# 3w-rgb-led-connector-mk-5_1.net
KiCad netlist of a schematic drawn in EAGLE
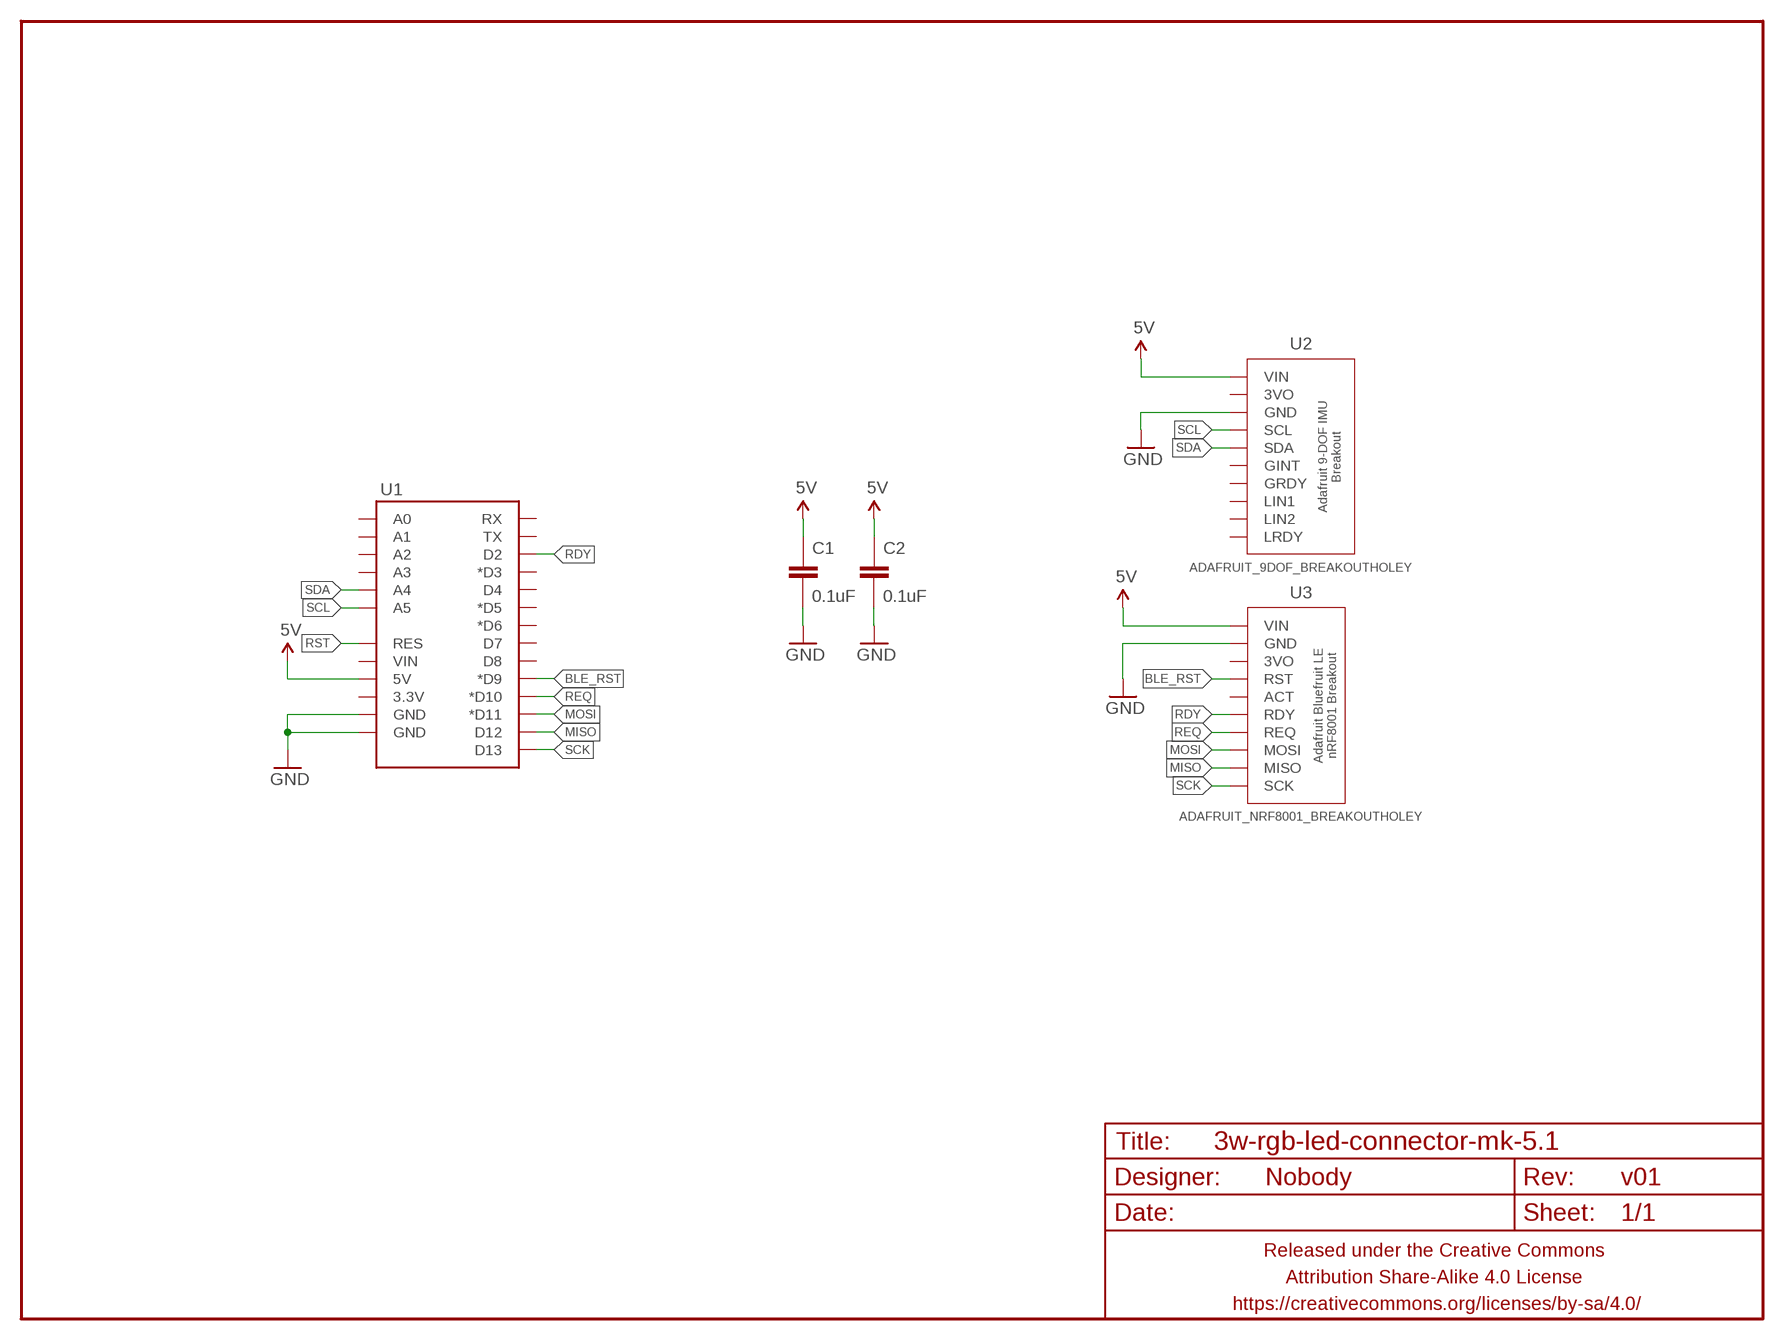
[diagram p0: schematic, sheet 1]

(export (version "E")
  (design (tool "Eeschema 10.0.6"))
  (components
    (comp (ref "C1")
      (value "0.1uF")
      (footprint "eagle-import:C025-024X044")
      (libsource (lib "eagle-import") (part "CAPACITOR-CERAMIC025-024X044"))
    )
    (comp (ref "C2")
      (value "0.1uF")
      (footprint "eagle-import:C025-024X044")
      (libsource (lib "eagle-import") (part "CAPACITOR-CERAMIC025-024X044"))
    )
    (comp (ref "FRAME1")
      (value "FRAME-LETTERNO_PACKAGE")
      (footprint "eagle-import:DUMMY")
      (fields (field (name "DESIGNER") "Nobody"))
      (libsource (lib "eagle-import") (part "FRAME-LETTERNO_PACKAGE"))
    )
    (comp (ref "U1")
      (value "ARDUINO_SHIELD_SMALLER")
      (footprint "eagle-import:ARDUINO_SHIELD_NOOUTLINE_INSIDE_SMALLER")
      (libsource (lib "eagle-import") (part "ARDUINO_SHIELD_SMALLER"))
    )
    (comp (ref "U2")
      (value "ADAFRUIT_9DOF_BREAKOUTHOLEY")
      (footprint "eagle-import:ADAFRUIT_9DOF_BREAKOUT_HOLEY")
      (libsource (lib "eagle-import") (part "ADAFRUIT_9DOF_BREAKOUTHOLEY"))
    )
    (comp (ref "U3")
      (value "ADAFRUIT_NRF8001_BREAKOUTHOLEY")
      (footprint "eagle-import:ADAFRUIT_NRF8001_HOLEY")
      (libsource (lib "eagle-import") (part "ADAFRUIT_NRF8001_BREAKOUTHOLEY"))
    )
  )
  (nets
    (net (code "1") (name "5V") (class "Default")
      (node (ref "C1") (pin "1") (pinfunction "1_1") (pintype "passive"))
      (node (ref "C2") (pin "1") (pinfunction "1_1") (pintype "passive"))
      (node (ref "U1") (pin "5V") (pinfunction "5V_5V") (pintype "bidirectional"))
      (node (ref "U2") (pin "VIN") (pinfunction "VIN_VIN") (pintype "bidirectional"))
      (node (ref "U3") (pin "VIN") (pinfunction "VIN_VIN") (pintype "bidirectional"))
    )
    (net (code "2") (name "BLE_RST") (class "Default")
      (node (ref "U1") (pin "D9") (pinfunction "*D9_D9") (pintype "bidirectional"))
      (node (ref "U3") (pin "RST") (pinfunction "RST_RST") (pintype "bidirectional"))
    )
    (net (code "3") (name "GND") (class "Default")
      (node (ref "C1") (pin "2") (pinfunction "2_2") (pintype "passive"))
      (node (ref "C2") (pin "2") (pinfunction "2_2") (pintype "passive"))
      (node (ref "U1") (pin "GND@0") (pinfunction "GND_GND@0") (pintype "bidirectional"))
      (node (ref "U1") (pin "GND@1") (pinfunction "GND_GND@1") (pintype "bidirectional"))
      (node (ref "U2") (pin "GND") (pinfunction "GND_GND") (pintype "bidirectional"))
      (node (ref "U3") (pin "GND") (pinfunction "GND_GND") (pintype "bidirectional"))
    )
    (net (code "4") (name "MISO") (class "Default")
      (node (ref "U1") (pin "D12") (pinfunction "D12_D12") (pintype "bidirectional"))
      (node (ref "U3") (pin "MISO") (pinfunction "MISO_MISO") (pintype "bidirectional"))
    )
    (net (code "5") (name "MOSI") (class "Default")
      (node (ref "U1") (pin "D11") (pinfunction "*D11_D11") (pintype "bidirectional"))
      (node (ref "U3") (pin "MOSI") (pinfunction "MOSI_MOSI") (pintype "bidirectional"))
    )
    (net (code "6") (name "RDY") (class "Default")
      (node (ref "U1") (pin "D2") (pinfunction "D2_D2") (pintype "bidirectional"))
      (node (ref "U3") (pin "RDY") (pinfunction "RDY_RDY") (pintype "bidirectional"))
    )
    (net (code "7") (name "REQ") (class "Default")
      (node (ref "U1") (pin "D10") (pinfunction "*D10_D10") (pintype "bidirectional"))
      (node (ref "U3") (pin "REQ") (pinfunction "REQ_REQ") (pintype "bidirectional"))
    )
    (net (code "8") (name "RST") (class "Default")
      (node (ref "U1") (pin "RES") (pinfunction "RES_RES") (pintype "bidirectional"))
    )
    (net (code "9") (name "SCK") (class "Default")
      (node (ref "U1") (pin "D13") (pinfunction "D13_D13") (pintype "bidirectional"))
      (node (ref "U3") (pin "SCK") (pinfunction "SCK_SCK") (pintype "bidirectional"))
    )
    (net (code "10") (name "SCL") (class "Default")
      (node (ref "U1") (pin "A5") (pinfunction "A5_A5") (pintype "bidirectional"))
      (node (ref "U2") (pin "SCL") (pinfunction "SCL_SCL") (pintype "bidirectional"))
    )
    (net (code "11") (name "SDA") (class "Default")
      (node (ref "U1") (pin "A4") (pinfunction "A4_A4") (pintype "bidirectional"))
      (node (ref "U2") (pin "SDA") (pinfunction "SDA_SDA") (pintype "bidirectional"))
    )
    (net (code "12") (name "unconnected-(U1-*D3-PadD3)") (class "Default")
      (node (ref "U1") (pin "D3") (pinfunction "*D3_D3") (pintype "bidirectional"))
    )
    (net (code "13") (name "unconnected-(U1-*D5-PadD5)") (class "Default")
      (node (ref "U1") (pin "D5") (pinfunction "*D5_D5") (pintype "bidirectional"))
    )
    (net (code "14") (name "unconnected-(U1-*D6-PadD6)") (class "Default")
      (node (ref "U1") (pin "D6") (pinfunction "*D6_D6") (pintype "bidirectional"))
    )
    (net (code "15") (name "unconnected-(U1-Pad3.3V)") (class "Default")
      (node (ref "U1") (pin "3.3V") (pinfunction "3.3V_3.3V") (pintype "bidirectional"))
    )
    (net (code "16") (name "unconnected-(U1-PadA0)") (class "Default")
      (node (ref "U1") (pin "A0") (pinfunction "A0_A0") (pintype "bidirectional"))
    )
    (net (code "17") (name "unconnected-(U1-PadA1)") (class "Default")
      (node (ref "U1") (pin "A1") (pinfunction "A1_A1") (pintype "bidirectional"))
    )
    (net (code "18") (name "unconnected-(U1-PadA2)") (class "Default")
      (node (ref "U1") (pin "A2") (pinfunction "A2_A2") (pintype "bidirectional"))
    )
    (net (code "19") (name "unconnected-(U1-PadA3)") (class "Default")
      (node (ref "U1") (pin "A3") (pinfunction "A3_A3") (pintype "bidirectional"))
    )
    (net (code "20") (name "unconnected-(U1-PadD4)") (class "Default")
      (node (ref "U1") (pin "D4") (pinfunction "D4_D4") (pintype "bidirectional"))
    )
    (net (code "21") (name "unconnected-(U1-PadD7)") (class "Default")
      (node (ref "U1") (pin "D7") (pinfunction "D7_D7") (pintype "bidirectional"))
    )
    (net (code "22") (name "unconnected-(U1-PadD8)") (class "Default")
      (node (ref "U1") (pin "D8") (pinfunction "D8_D8") (pintype "bidirectional"))
    )
    (net (code "23") (name "unconnected-(U1-PadRX)") (class "Default")
      (node (ref "U1") (pin "RX") (pinfunction "RX_RX") (pintype "bidirectional"))
    )
    (net (code "24") (name "unconnected-(U1-PadTX)") (class "Default")
      (node (ref "U1") (pin "TX") (pinfunction "TX_TX") (pintype "bidirectional"))
    )
    (net (code "25") (name "unconnected-(U1-PadVIN)") (class "Default")
      (node (ref "U1") (pin "VIN") (pinfunction "VIN_VIN") (pintype "bidirectional"))
    )
    (net (code "26") (name "unconnected-(U2-Pad3VO)") (class "Default")
      (node (ref "U2") (pin "3VO") (pinfunction "3VO_3VO") (pintype "bidirectional"))
    )
    (net (code "27") (name "unconnected-(U2-PadGINT)") (class "Default")
      (node (ref "U2") (pin "GINT") (pinfunction "GINT_GINT") (pintype "bidirectional"))
    )
    (net (code "28") (name "unconnected-(U2-PadGRDY)") (class "Default")
      (node (ref "U2") (pin "GRDY") (pinfunction "GRDY_GRDY") (pintype "bidirectional"))
    )
    (net (code "29") (name "unconnected-(U2-PadLIN1)") (class "Default")
      (node (ref "U2") (pin "LIN1") (pinfunction "LIN1_LIN1") (pintype "bidirectional"))
    )
    (net (code "30") (name "unconnected-(U2-PadLIN2)") (class "Default")
      (node (ref "U2") (pin "LIN2") (pinfunction "LIN2_LIN2") (pintype "bidirectional"))
    )
    (net (code "31") (name "unconnected-(U2-PadLRDY)") (class "Default")
      (node (ref "U2") (pin "LRDY") (pinfunction "LRDY_LRDY") (pintype "bidirectional"))
    )
    (net (code "32") (name "unconnected-(U3-Pad3VO)") (class "Default")
      (node (ref "U3") (pin "3VO") (pinfunction "3VO_3VO") (pintype "bidirectional"))
    )
    (net (code "33") (name "unconnected-(U3-PadACT)") (class "Default")
      (node (ref "U3") (pin "ACT") (pinfunction "ACT_ACT") (pintype "bidirectional"))
    )
  )
)
